# BeagleBeer.net
KiCad netlist of a schematic drawn in EAGLE
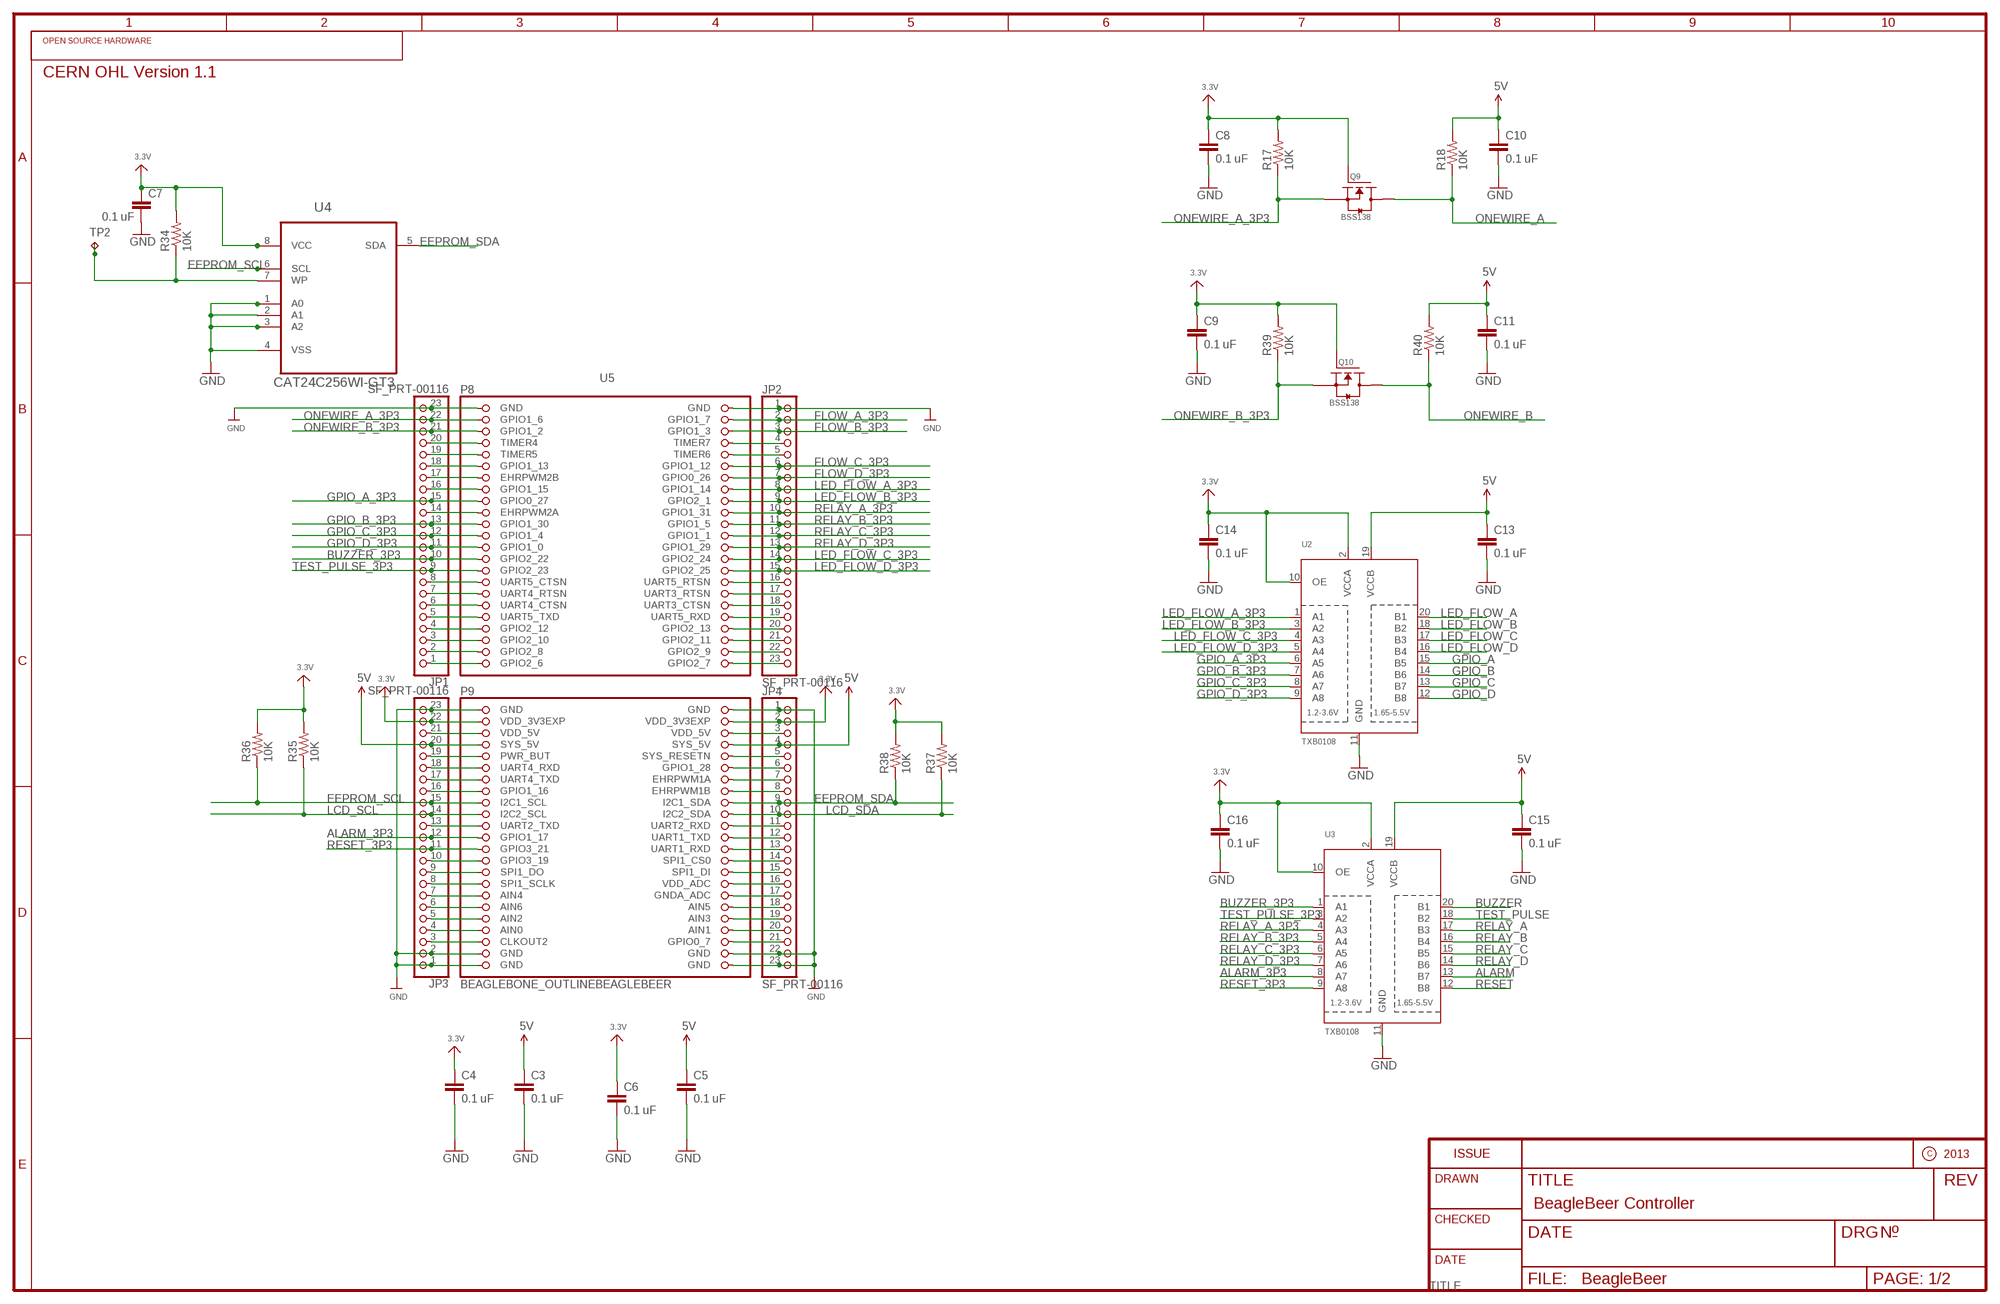
[diagram p0: schematic, sheet 1]
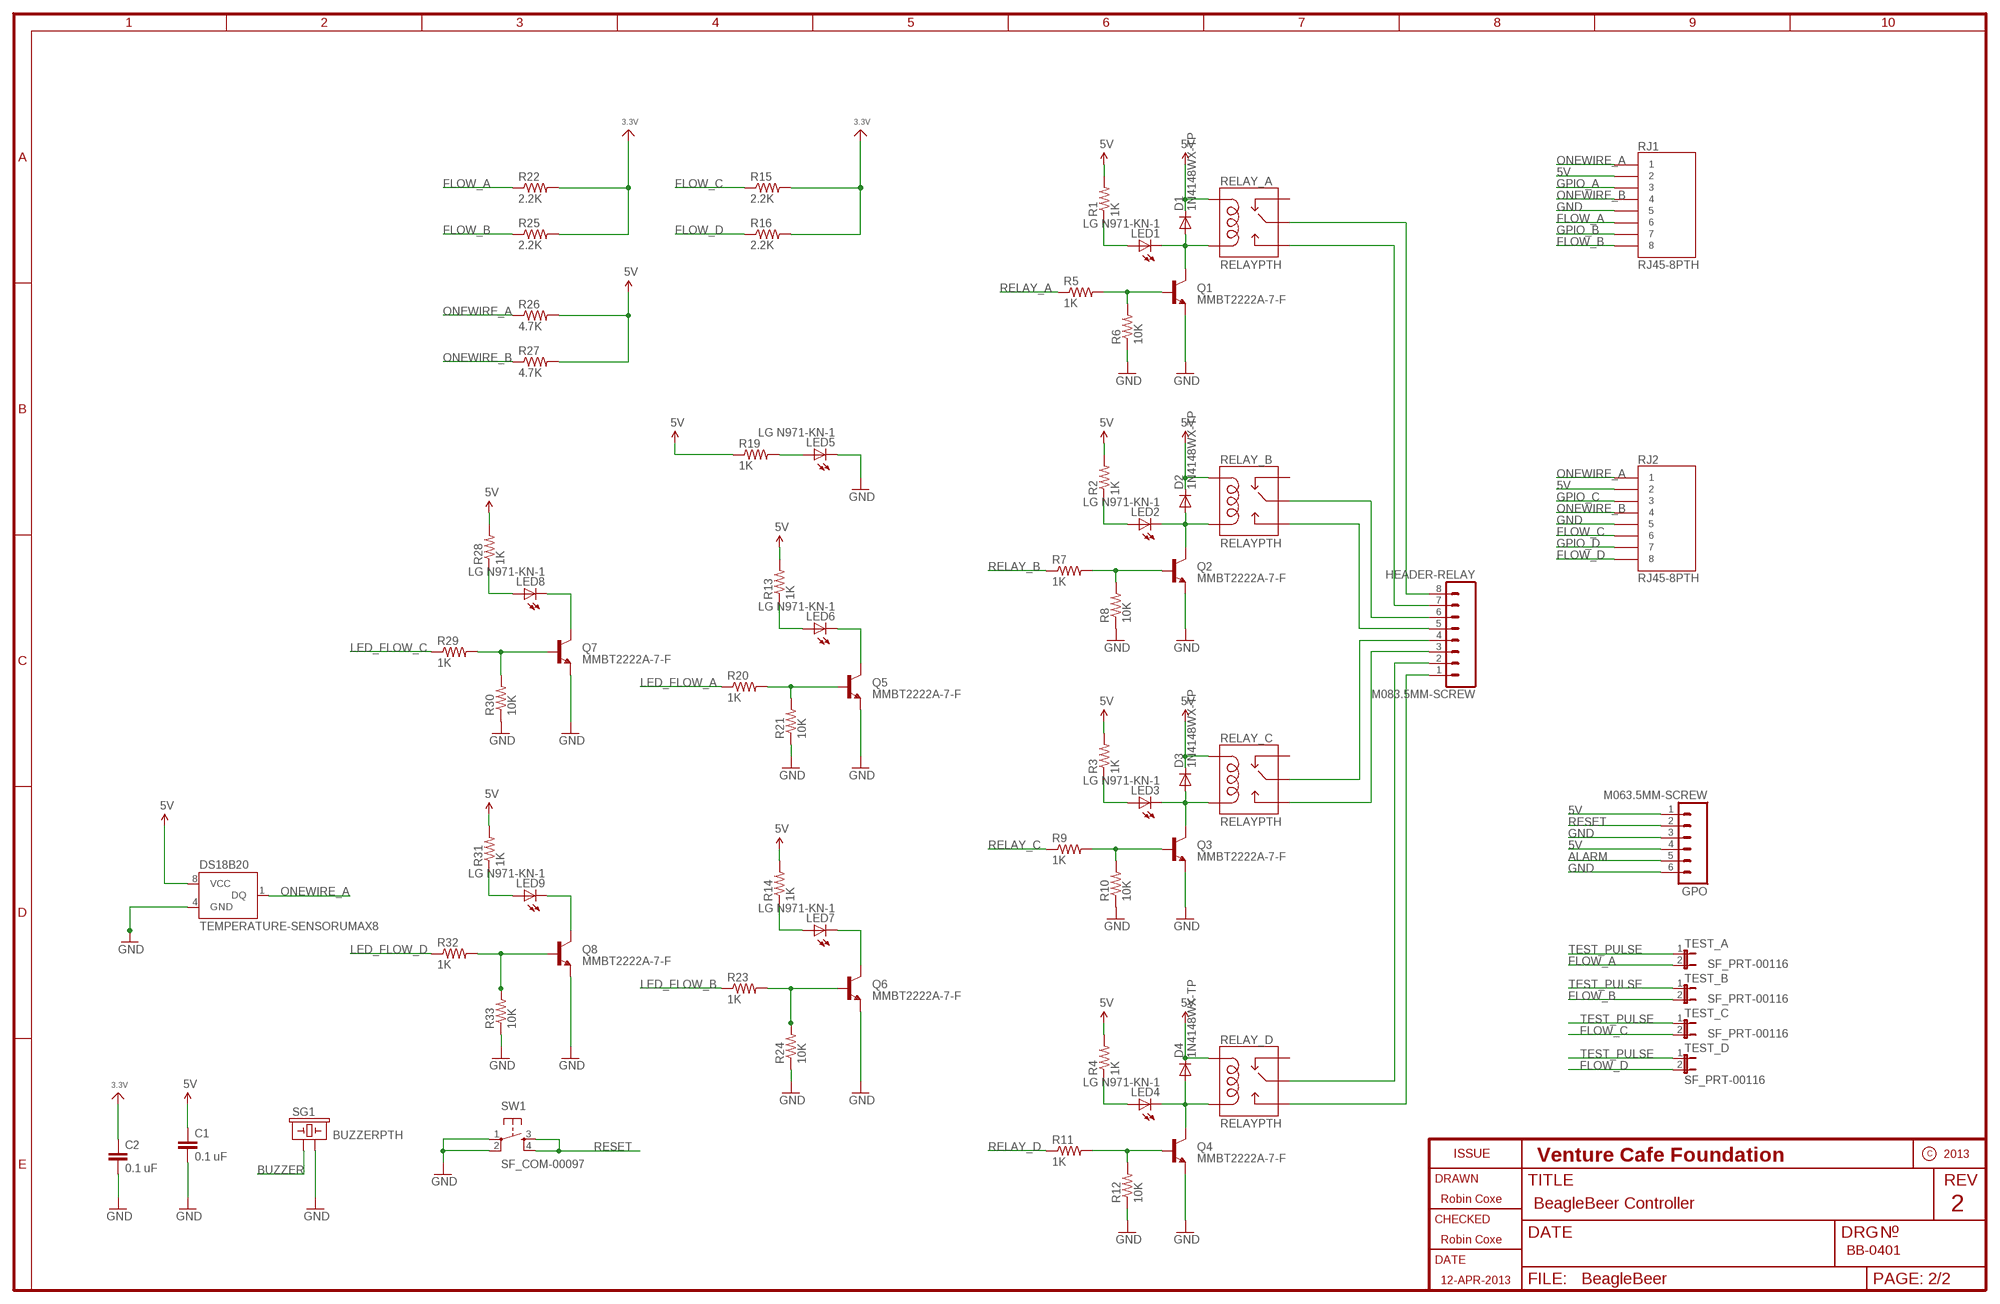
[diagram p1: schematic, sheet 2]

(export (version "E")
  (design (tool "Eeschema 10.0.6"))
  (components
    (comp (ref "C1")
      (value "0.1 uF")
      (footprint "eagle-import:0805")
      (libsource (lib "eagle-import") (part "CAP0805"))
    )
    (comp (ref "C2")
      (value "0.1 uF")
      (footprint "eagle-import:0805")
      (libsource (lib "eagle-import") (part "CAP0805"))
    )
    (comp (ref "D1")
      (value "1N4148WX-TP")
      (footprint "eagle-import:SOD-323")
      (libsource (lib "eagle-import") (part "DIODESOD"))
    )
    (comp (ref "D2")
      (value "1N4148WX-TP")
      (footprint "eagle-import:SOD-323")
      (libsource (lib "eagle-import") (part "DIODESOD"))
    )
    (comp (ref "D3")
      (value "1N4148WX-TP")
      (footprint "eagle-import:SOD-323")
      (libsource (lib "eagle-import") (part "DIODESOD"))
    )
    (comp (ref "D4")
      (value "1N4148WX-TP")
      (footprint "eagle-import:SOD-323")
      (libsource (lib "eagle-import") (part "DIODESOD"))
    )
    (comp (ref "GPO")
      (value "M063.5MM-SCREW")
      (footprint "eagle-import:SCREWTERMINAL-3.5MM-6")
      (libsource (lib "eagle-import") (part "M063.5MM-6"))
    )
    (comp (ref "HEADER-RELAY")
      (value "M083.5MM-SCREW")
      (footprint "eagle-import:SCREWTERMINAL-3.5MM-8")
      (libsource (lib "eagle-import") (part "M083.5MM-8"))
    )
    (comp (ref "LED1")
      (value "LG N971-KN-1")
      (footprint "eagle-import:LED-1206")
      (libsource (lib "eagle-import") (part "LED1206"))
    )
    (comp (ref "LED2")
      (value "LG N971-KN-1")
      (footprint "eagle-import:LED-1206")
      (libsource (lib "eagle-import") (part "LED1206"))
    )
    (comp (ref "LED3")
      (value "LG N971-KN-1")
      (footprint "eagle-import:LED-1206")
      (libsource (lib "eagle-import") (part "LED1206"))
    )
    (comp (ref "LED4")
      (value "LG N971-KN-1")
      (footprint "eagle-import:LED-1206")
      (libsource (lib "eagle-import") (part "LED1206"))
    )
    (comp (ref "LED5")
      (value "LG N971-KN-1")
      (footprint "eagle-import:LED-1206")
      (libsource (lib "eagle-import") (part "LED1206"))
    )
    (comp (ref "LED6")
      (value "LG N971-KN-1")
      (footprint "eagle-import:LED-1206")
      (libsource (lib "eagle-import") (part "LED1206"))
    )
    (comp (ref "LED7")
      (value "LG N971-KN-1")
      (footprint "eagle-import:LED-1206")
      (libsource (lib "eagle-import") (part "LED1206"))
    )
    (comp (ref "LED8")
      (value "LG N971-KN-1")
      (footprint "eagle-import:LED-1206")
      (libsource (lib "eagle-import") (part "LED1206"))
    )
    (comp (ref "LED9")
      (value "LG N971-KN-1")
      (footprint "eagle-import:LED-1206")
      (libsource (lib "eagle-import") (part "LED1206"))
    )
    (comp (ref "Q1")
      (value "MMBT2222A-7-F")
      (footprint "eagle-import:SOT23-3")
      (libsource (lib "eagle-import") (part "TRANSISTOR_NPNSOT23-3"))
    )
    (comp (ref "Q2")
      (value "MMBT2222A-7-F")
      (footprint "eagle-import:SOT23-3")
      (libsource (lib "eagle-import") (part "TRANSISTOR_NPNSOT23-3"))
    )
    (comp (ref "Q3")
      (value "MMBT2222A-7-F")
      (footprint "eagle-import:SOT23-3")
      (libsource (lib "eagle-import") (part "TRANSISTOR_NPNSOT23-3"))
    )
    (comp (ref "Q4")
      (value "MMBT2222A-7-F")
      (footprint "eagle-import:SOT23-3")
      (libsource (lib "eagle-import") (part "TRANSISTOR_NPNSOT23-3"))
    )
    (comp (ref "Q5")
      (value "MMBT2222A-7-F")
      (footprint "eagle-import:SOT23-3")
      (libsource (lib "eagle-import") (part "TRANSISTOR_NPNSOT23-3"))
    )
    (comp (ref "Q6")
      (value "MMBT2222A-7-F")
      (footprint "eagle-import:SOT23-3")
      (libsource (lib "eagle-import") (part "TRANSISTOR_NPNSOT23-3"))
    )
    (comp (ref "Q7")
      (value "MMBT2222A-7-F")
      (footprint "eagle-import:SOT23-3")
      (libsource (lib "eagle-import") (part "TRANSISTOR_NPNSOT23-3"))
    )
    (comp (ref "Q8")
      (value "MMBT2222A-7-F")
      (footprint "eagle-import:SOT23-3")
      (libsource (lib "eagle-import") (part "TRANSISTOR_NPNSOT23-3"))
    )
    (comp (ref "R1")
      (value "1K")
      (footprint "eagle-import:0805")
      (libsource (lib "eagle-import") (part "RESISTOR0805-RES"))
    )
    (comp (ref "R2")
      (value "1K")
      (footprint "eagle-import:0805")
      (libsource (lib "eagle-import") (part "RESISTOR0805-RES"))
    )
    (comp (ref "R3")
      (value "1K")
      (footprint "eagle-import:0805")
      (libsource (lib "eagle-import") (part "RESISTOR0805-RES"))
    )
    (comp (ref "R4")
      (value "1K")
      (footprint "eagle-import:0805")
      (libsource (lib "eagle-import") (part "RESISTOR0805-RES"))
    )
    (comp (ref "R5")
      (value "1K")
      (footprint "eagle-import:0805")
      (libsource (lib "eagle-import") (part "RESISTOR0805-RES"))
    )
    (comp (ref "R6")
      (value "10K")
      (footprint "eagle-import:0805")
      (libsource (lib "eagle-import") (part "RESISTOR0805-RES"))
    )
    (comp (ref "R7")
      (value "1K")
      (footprint "eagle-import:0805")
      (libsource (lib "eagle-import") (part "RESISTOR0805-RES"))
    )
    (comp (ref "R8")
      (value "10K")
      (footprint "eagle-import:0805")
      (libsource (lib "eagle-import") (part "RESISTOR0805-RES"))
    )
    (comp (ref "R9")
      (value "1K")
      (footprint "eagle-import:0805")
      (libsource (lib "eagle-import") (part "RESISTOR0805-RES"))
    )
    (comp (ref "R10")
      (value "10K")
      (footprint "eagle-import:0805")
      (libsource (lib "eagle-import") (part "RESISTOR0805-RES"))
    )
    (comp (ref "R11")
      (value "1K")
      (footprint "eagle-import:0805")
      (libsource (lib "eagle-import") (part "RESISTOR0805-RES"))
    )
    (comp (ref "R12")
      (value "10K")
      (footprint "eagle-import:0805")
      (libsource (lib "eagle-import") (part "RESISTOR0805-RES"))
    )
    (comp (ref "R13")
      (value "1K")
      (footprint "eagle-import:0805")
      (libsource (lib "eagle-import") (part "RESISTOR0805-RES"))
    )
    (comp (ref "R14")
      (value "1K")
      (footprint "eagle-import:0805")
      (libsource (lib "eagle-import") (part "RESISTOR0805-RES"))
    )
    (comp (ref "R15")
      (value "2.2K")
      (footprint "eagle-import:0805")
      (libsource (lib "eagle-import") (part "RESISTOR0805-RES"))
    )
    (comp (ref "R16")
      (value "2.2K")
      (footprint "eagle-import:0805")
      (libsource (lib "eagle-import") (part "RESISTOR0805-RES"))
    )
    (comp (ref "R19")
      (value "1K")
      (footprint "eagle-import:0805")
      (libsource (lib "eagle-import") (part "RESISTOR0805-RES"))
    )
    (comp (ref "R20")
      (value "1K")
      (footprint "eagle-import:0805")
      (libsource (lib "eagle-import") (part "RESISTOR0805-RES"))
    )
    (comp (ref "R21")
      (value "10K")
      (footprint "eagle-import:0805")
      (libsource (lib "eagle-import") (part "RESISTOR0805-RES"))
    )
    (comp (ref "R22")
      (value "2.2K")
      (footprint "eagle-import:0805")
      (libsource (lib "eagle-import") (part "RESISTOR0805-RES"))
    )
    (comp (ref "R23")
      (value "1K")
      (footprint "eagle-import:0805")
      (libsource (lib "eagle-import") (part "RESISTOR0805-RES"))
    )
    (comp (ref "R24")
      (value "10K")
      (footprint "eagle-import:0805")
      (libsource (lib "eagle-import") (part "RESISTOR0805-RES"))
    )
    (comp (ref "R25")
      (value "2.2K")
      (footprint "eagle-import:0805")
      (libsource (lib "eagle-import") (part "RESISTOR0805-RES"))
    )
    (comp (ref "R26")
      (value "4.7K")
      (footprint "eagle-import:0805")
      (libsource (lib "eagle-import") (part "RESISTOR0805-RES"))
    )
    (comp (ref "R27")
      (value "4.7K")
      (footprint "eagle-import:0805")
      (libsource (lib "eagle-import") (part "RESISTOR0805-RES"))
    )
    (comp (ref "R28")
      (value "1K")
      (footprint "eagle-import:0805")
      (libsource (lib "eagle-import") (part "RESISTOR0805-RES"))
    )
    (comp (ref "R29")
      (value "1K")
      (footprint "eagle-import:0805")
      (libsource (lib "eagle-import") (part "RESISTOR0805-RES"))
    )
    (comp (ref "R30")
      (value "10K")
      (footprint "eagle-import:0805")
      (libsource (lib "eagle-import") (part "RESISTOR0805-RES"))
    )
    (comp (ref "R31")
      (value "1K")
      (footprint "eagle-import:0805")
      (libsource (lib "eagle-import") (part "RESISTOR0805-RES"))
    )
    (comp (ref "R32")
      (value "1K")
      (footprint "eagle-import:0805")
      (libsource (lib "eagle-import") (part "RESISTOR0805-RES"))
    )
    (comp (ref "R33")
      (value "10K")
      (footprint "eagle-import:0805")
      (libsource (lib "eagle-import") (part "RESISTOR0805-RES"))
    )
    (comp (ref "RELAY_A")
      (value "RELAYPTH")
      (footprint "eagle-import:RELAY-G5Q")
      (libsource (lib "eagle-import") (part "RELAYPTH"))
    )
    (comp (ref "RELAY_B")
      (value "RELAYPTH")
      (footprint "eagle-import:RELAY-G5Q")
      (libsource (lib "eagle-import") (part "RELAYPTH"))
    )
    (comp (ref "RELAY_C")
      (value "RELAYPTH")
      (footprint "eagle-import:RELAY-G5Q")
      (libsource (lib "eagle-import") (part "RELAYPTH"))
    )
    (comp (ref "RELAY_D")
      (value "RELAYPTH")
      (footprint "eagle-import:RELAY-G5Q")
      (libsource (lib "eagle-import") (part "RELAYPTH"))
    )
    (comp (ref "RJ1")
      (value "RJ45-8PTH")
      (footprint "eagle-import:RJ45-8")
      (libsource (lib "eagle-import") (part "RJ45-8PTH"))
    )
    (comp (ref "RJ2")
      (value "RJ45-8PTH")
      (footprint "eagle-import:RJ45-8")
      (libsource (lib "eagle-import") (part "RJ45-8PTH"))
    )
    (comp (ref "SG1")
      (value "BUZZERPTH")
      (footprint "eagle-import:BUZZER-12MM")
      (libsource (lib "eagle-import") (part "BUZZERPTH"))
    )
    (comp (ref "SW1")
      (value "SF_COM-00097")
      (footprint "eagle-import:TACTILE-PTH")
      (libsource (lib "eagle-import") (part "TAC_SWITCHPTH"))
    )
    (comp (ref "TEST_A")
      (value "SF_PRT-00116")
      (footprint "eagle-import:1X02")
      (libsource (lib "eagle-import") (part "JUMPER-2PTH"))
    )
    (comp (ref "TEST_B")
      (value "SF_PRT-00116")
      (footprint "eagle-import:1X02")
      (libsource (lib "eagle-import") (part "JUMPER-2PTH"))
    )
    (comp (ref "TEST_C")
      (value "SF_PRT-00116")
      (footprint "eagle-import:1X02")
      (libsource (lib "eagle-import") (part "JUMPER-2PTH"))
    )
    (comp (ref "TEST_D")
      (value "SF_PRT-00116")
      (footprint "eagle-import:1X02")
      (libsource (lib "eagle-import") (part "JUMPER-2PTH"))
    )
    (comp (ref "U1")
      (value "TEMPERATURE-SENSORUMAX8")
      (footprint "eagle-import:UMAX8")
      (libsource (lib "eagle-import") (part "TEMPERATURE-SENSORUMAX8"))
    )
    (comp (ref "C3")
      (value "0.1 uF")
      (footprint "eagle-import:0805")
      (libsource (lib "eagle-import") (part "CAP0805"))
    )
    (comp (ref "C4")
      (value "0.1 uF")
      (footprint "eagle-import:0805")
      (libsource (lib "eagle-import") (part "CAP0805"))
    )
    (comp (ref "C5")
      (value "0.1 uF")
      (footprint "eagle-import:0805")
      (libsource (lib "eagle-import") (part "CAP0805"))
    )
    (comp (ref "C6")
      (value "0.1 uF")
      (footprint "eagle-import:0805")
      (libsource (lib "eagle-import") (part "CAP0805"))
    )
    (comp (ref "C7")
      (value "0.1 uF")
      (footprint "eagle-import:0805")
      (libsource (lib "eagle-import") (part "CAP0805"))
    )
    (comp (ref "C8")
      (value "0.1 uF")
      (footprint "eagle-import:0805")
      (libsource (lib "eagle-import") (part "CAP0805"))
    )
    (comp (ref "C9")
      (value "0.1 uF")
      (footprint "eagle-import:0805")
      (libsource (lib "eagle-import") (part "CAP0805"))
    )
    (comp (ref "C10")
      (value "0.1 uF")
      (footprint "eagle-import:0805")
      (libsource (lib "eagle-import") (part "CAP0805"))
    )
    (comp (ref "C11")
      (value "0.1 uF")
      (footprint "eagle-import:0805")
      (libsource (lib "eagle-import") (part "CAP0805"))
    )
    (comp (ref "C13")
      (value "0.1 uF")
      (footprint "eagle-import:0805")
      (libsource (lib "eagle-import") (part "CAP0805"))
    )
    (comp (ref "C14")
      (value "0.1 uF")
      (footprint "eagle-import:0805")
      (libsource (lib "eagle-import") (part "CAP0805"))
    )
    (comp (ref "C15")
      (value "0.1 uF")
      (footprint "eagle-import:0805")
      (libsource (lib "eagle-import") (part "CAP0805"))
    )
    (comp (ref "C16")
      (value "0.1 uF")
      (footprint "eagle-import:0805")
      (libsource (lib "eagle-import") (part "CAP0805"))
    )
    (comp (ref "JP1")
      (value "SF_PRT-00116")
      (footprint "eagle-import:1X23_ROUND_70MIL")
      (libsource (lib "eagle-import") (part "HEADER-1X23"))
    )
    (comp (ref "JP2")
      (value "SF_PRT-00116")
      (footprint "eagle-import:1X23_ROUND_70MIL")
      (libsource (lib "eagle-import") (part "HEADER-1X23"))
    )
    (comp (ref "JP3")
      (value "SF_PRT-00116")
      (footprint "eagle-import:1X23_ROUND_70MIL")
      (libsource (lib "eagle-import") (part "HEADER-1X23"))
    )
    (comp (ref "JP4")
      (value "SF_PRT-00116")
      (footprint "eagle-import:1X23_ROUND_70MIL")
      (libsource (lib "eagle-import") (part "HEADER-1X23"))
    )
    (comp (ref "Q9")
      (value "BSS138")
      (footprint "eagle-import:SOT323")
      (libsource (lib "eagle-import") (part "MOSFET-N-GDS-D-SOT323"))
    )
    (comp (ref "Q10")
      (value "BSS138")
      (footprint "eagle-import:SOT323")
      (libsource (lib "eagle-import") (part "MOSFET-N-GDS-D-SOT323"))
    )
    (comp (ref "R17")
      (value "10K")
      (footprint "eagle-import:0805")
      (libsource (lib "eagle-import") (part "RESISTOR0805-RES"))
    )
    (comp (ref "R18")
      (value "10K")
      (footprint "eagle-import:0805")
      (libsource (lib "eagle-import") (part "RESISTOR0805-RES"))
    )
    (comp (ref "R34")
      (value "10K")
      (footprint "eagle-import:0805")
      (libsource (lib "eagle-import") (part "RESISTOR0805-RES"))
    )
    (comp (ref "R35")
      (value "10K")
      (footprint "eagle-import:0805")
      (libsource (lib "eagle-import") (part "RESISTOR0805-RES"))
    )
    (comp (ref "R36")
      (value "10K")
      (footprint "eagle-import:0805")
      (libsource (lib "eagle-import") (part "RESISTOR0805-RES"))
    )
    (comp (ref "R37")
      (value "10K")
      (footprint "eagle-import:0805")
      (libsource (lib "eagle-import") (part "RESISTOR0805-RES"))
    )
    (comp (ref "R38")
      (value "10K")
      (footprint "eagle-import:0805")
      (libsource (lib "eagle-import") (part "RESISTOR0805-RES"))
    )
    (comp (ref "R39")
      (value "10K")
      (footprint "eagle-import:0805")
      (libsource (lib "eagle-import") (part "RESISTOR0805-RES"))
    )
    (comp (ref "R40")
      (value "10K")
      (footprint "eagle-import:0805")
      (libsource (lib "eagle-import") (part "RESISTOR0805-RES"))
    )
    (comp (ref "TP2")
      (value "TPTP18SQ")
      (footprint "eagle-import:TP18SQ")
      (libsource (lib "eagle-import") (part "TPTP18SQ"))
    )
    (comp (ref "U2")
      (value "TXB0108")
      (footprint "eagle-import:TSSOP20")
      (libsource (lib "eagle-import") (part "TXB0108PWR"))
    )
    (comp (ref "U3")
      (value "TXB0108")
      (footprint "eagle-import:TSSOP20")
      (libsource (lib "eagle-import") (part "TXB0108PWR"))
    )
    (comp (ref "U4")
      (value "CAT24C256WI-GT3")
      (footprint "eagle-import:SOIC127P600X175-8N")
      (libsource (lib "eagle-import") (part "CAT24C256WI-GT3"))
    )
    (comp (ref "U5")
      (value "BEAGLEBONE_OUTLINEBEAGLEBEER")
      (footprint "eagle-import:BEAGLEBEER_SHIELD")
      (libsource (lib "eagle-import") (part "BEAGLEBONE_OUTLINEBEAGLEBEER"))
    )
  )
  (nets
    (net (code "1") (name "3.3V") (class "Default")
      (node (ref "C14") (pin "1") (pinfunction "1_1") (pintype "passive"))
      (node (ref "C16") (pin "1") (pinfunction "1_1") (pintype "passive"))
      (node (ref "C2") (pin "1") (pinfunction "1_1") (pintype "passive"))
      (node (ref "C4") (pin "1") (pinfunction "1_1") (pintype "passive"))
      (node (ref "C6") (pin "1") (pinfunction "1_1") (pintype "passive"))
      (node (ref "C7") (pin "1") (pinfunction "1_1") (pintype "passive"))
      (node (ref "C8") (pin "1") (pinfunction "1_1") (pintype "passive"))
      (node (ref "C9") (pin "1") (pinfunction "1_1") (pintype "passive"))
      (node (ref "JP3") (pin "22") (pinfunction "22_22") (pintype "passive"))
      (node (ref "JP4") (pin "2") (pinfunction "2_2") (pintype "passive"))
      (node (ref "Q10") (pin "1") (pinfunction "G_1") (pintype "passive"))
      (node (ref "Q9") (pin "1") (pinfunction "G_1") (pintype "passive"))
      (node (ref "R15") (pin "2") (pinfunction "2_2") (pintype "passive"))
      (node (ref "R16") (pin "2") (pinfunction "2_2") (pintype "passive"))
      (node (ref "R17") (pin "2") (pinfunction "2_2") (pintype "passive"))
      (node (ref "R22") (pin "2") (pinfunction "2_2") (pintype "passive"))
      (node (ref "R25") (pin "2") (pinfunction "2_2") (pintype "passive"))
      (node (ref "R34") (pin "2") (pinfunction "2_2") (pintype "passive"))
      (node (ref "R35") (pin "2") (pinfunction "2_2") (pintype "passive"))
      (node (ref "R36") (pin "2") (pinfunction "2_2") (pintype "passive"))
      (node (ref "R37") (pin "2") (pinfunction "2_2") (pintype "passive"))
      (node (ref "R38") (pin "2") (pinfunction "2_2") (pintype "passive"))
      (node (ref "R39") (pin "2") (pinfunction "2_2") (pintype "passive"))
      (node (ref "U2") (pin "10") (pinfunction "OE_10") (pintype "bidirectional"))
      (node (ref "U2") (pin "2") (pinfunction "VCCA_2") (pintype "bidirectional"))
      (node (ref "U3") (pin "10") (pinfunction "OE_10") (pintype "bidirectional"))
      (node (ref "U3") (pin "2") (pinfunction "VCCA_2") (pintype "bidirectional"))
      (node (ref "U4") (pin "8") (pinfunction "VCC_8") (pintype "power_in"))
      (node (ref "U5") (pin "49") (pinfunction "VDD_3V3EXP_49") (pintype "power_in"))
      (node (ref "U5") (pin "50") (pinfunction "VDD_3V3EXP_50") (pintype "power_in"))
    )
    (net (code "2") (name "5V") (class "Default")
      (node (ref "C1") (pin "1") (pinfunction "1_1") (pintype "passive"))
      (node (ref "C10") (pin "1") (pinfunction "1_1") (pintype "passive"))
      (node (ref "C11") (pin "1") (pinfunction "1_1") (pintype "passive"))
      (node (ref "C13") (pin "1") (pinfunction "1_1") (pintype "passive"))
      (node (ref "C15") (pin "1") (pinfunction "1_1") (pintype "passive"))
      (node (ref "C3") (pin "1") (pinfunction "1_1") (pintype "passive"))
      (node (ref "C5") (pin "1") (pinfunction "1_1") (pintype "passive"))
      (node (ref "D1") (pin "1") (pinfunction "C_1") (pintype "passive"))
      (node (ref "D2") (pin "1") (pinfunction "C_1") (pintype "passive"))
      (node (ref "D3") (pin "1") (pinfunction "C_1") (pintype "passive"))
      (node (ref "D4") (pin "1") (pinfunction "C_1") (pintype "passive"))
      (node (ref "GPO") (pin "1") (pinfunction "1_1") (pintype "passive"))
      (node (ref "GPO") (pin "4") (pinfunction "4_4") (pintype "passive"))
      (node (ref "JP3") (pin "20") (pinfunction "20_20") (pintype "passive"))
      (node (ref "JP4") (pin "4") (pinfunction "4_4") (pintype "passive"))
      (node (ref "R1") (pin "2") (pinfunction "2_2") (pintype "passive"))
      (node (ref "R13") (pin "2") (pinfunction "2_2") (pintype "passive"))
      (node (ref "R14") (pin "2") (pinfunction "2_2") (pintype "passive"))
      (node (ref "R18") (pin "2") (pinfunction "2_2") (pintype "passive"))
      (node (ref "R19") (pin "1") (pinfunction "1_1") (pintype "passive"))
      (node (ref "R2") (pin "2") (pinfunction "2_2") (pintype "passive"))
      (node (ref "R26") (pin "2") (pinfunction "2_2") (pintype "passive"))
      (node (ref "R27") (pin "2") (pinfunction "2_2") (pintype "passive"))
      (node (ref "R28") (pin "2") (pinfunction "2_2") (pintype "passive"))
      (node (ref "R3") (pin "2") (pinfunction "2_2") (pintype "passive"))
      (node (ref "R31") (pin "2") (pinfunction "2_2") (pintype "passive"))
      (node (ref "R4") (pin "2") (pinfunction "2_2") (pintype "passive"))
      (node (ref "R40") (pin "2") (pinfunction "2_2") (pintype "passive"))
      (node (ref "RELAY_A") (pin "5") (pinfunction "COIL1_5") (pintype "bidirectional"))
      (node (ref "RELAY_B") (pin "5") (pinfunction "COIL1_5") (pintype "bidirectional"))
      (node (ref "RELAY_C") (pin "5") (pinfunction "COIL1_5") (pintype "bidirectional"))
      (node (ref "RELAY_D") (pin "5") (pinfunction "COIL1_5") (pintype "bidirectional"))
      (node (ref "RJ1") (pin "2") (pinfunction "2_2") (pintype "bidirectional"))
      (node (ref "RJ2") (pin "2") (pinfunction "2_2") (pintype "bidirectional"))
      (node (ref "U1") (pin "8") (pinfunction "VCC_8") (pintype "bidirectional"))
      (node (ref "U2") (pin "19") (pinfunction "VCCB_19") (pintype "bidirectional"))
      (node (ref "U3") (pin "19") (pinfunction "VCCB_19") (pintype "bidirectional"))
      (node (ref "U5") (pin "53") (pinfunction "SYS_5V_53") (pintype "passive"))
      (node (ref "U5") (pin "54") (pinfunction "SYS_5V_54") (pintype "passive"))
    )
    (net (code "3") (name "ALARM") (class "Default")
      (node (ref "GPO") (pin "5") (pinfunction "5_5") (pintype "passive"))
      (node (ref "U3") (pin "13") (pinfunction "B7_13") (pintype "bidirectional"))
    )
    (net (code "4") (name "ALARM_3P3") (class "Default")
      (node (ref "JP3") (pin "12") (pinfunction "12_12") (pintype "passive"))
      (node (ref "U3") (pin "8") (pinfunction "A7_8") (pintype "bidirectional"))
      (node (ref "U5") (pin "69") (pinfunction "GPIO1_17_69") (pintype "passive"))
    )
    (net (code "5") (name "BUZZER") (class "Default")
      (node (ref "SG1") (pin "+") (pinfunction "1_+") (pintype "passive"))
      (node (ref "U3") (pin "20") (pinfunction "B1_20") (pintype "bidirectional"))
    )
    (net (code "6") (name "BUZZER_3P3") (class "Default")
      (node (ref "JP1") (pin "10") (pinfunction "10_10") (pintype "passive"))
      (node (ref "U3") (pin "1") (pinfunction "A1_1") (pintype "bidirectional"))
      (node (ref "U5") (pin "27") (pinfunction "GPIO2_22_27") (pintype "passive"))
    )
    (net (code "7") (name "EEPROM_SCL") (class "Default")
      (node (ref "JP3") (pin "15") (pinfunction "15_15") (pintype "passive"))
      (node (ref "R36") (pin "1") (pinfunction "1_1") (pintype "passive"))
      (node (ref "U4") (pin "6") (pinfunction "SCL_6") (pintype "input"))
      (node (ref "U5") (pin "63") (pinfunction "I2C1_SCL_63") (pintype "passive"))
    )
    (net (code "8") (name "EEPROM_SDA") (class "Default")
      (node (ref "JP4") (pin "9") (pinfunction "9_9") (pintype "passive"))
      (node (ref "R38") (pin "1") (pinfunction "1_1") (pintype "passive"))
      (node (ref "U4") (pin "5") (pinfunction "SDA_5") (pintype "bidirectional"))
      (node (ref "U5") (pin "64") (pinfunction "I2C1_SDA_64") (pintype "passive"))
    )
    (net (code "9") (name "FLOW_A") (class "Default")
      (node (ref "R22") (pin "1") (pinfunction "1_1") (pintype "passive"))
      (node (ref "RJ1") (pin "6") (pinfunction "6_6") (pintype "bidirectional"))
      (node (ref "TEST_A") (pin "2") (pinfunction "2_2") (pintype "passive"))
    )
    (net (code "10") (name "FLOW_A_3P3") (class "Default")
      (node (ref "JP2") (pin "2") (pinfunction "2_2") (pintype "passive"))
      (node (ref "U5") (pin "4") (pinfunction "GPIO1_7_4") (pintype "power_in"))
    )
    (net (code "11") (name "FLOW_B") (class "Default")
      (node (ref "R25") (pin "1") (pinfunction "1_1") (pintype "passive"))
      (node (ref "RJ1") (pin "8") (pinfunction "8_8") (pintype "bidirectional"))
      (node (ref "TEST_B") (pin "2") (pinfunction "2_2") (pintype "passive"))
    )
    (net (code "12") (name "FLOW_B_3P3") (class "Default")
      (node (ref "JP2") (pin "3") (pinfunction "3_3") (pintype "passive"))
      (node (ref "U5") (pin "6") (pinfunction "GPIO1_3_6") (pintype "passive"))
    )
    (net (code "13") (name "FLOW_C") (class "Default")
      (node (ref "R15") (pin "1") (pinfunction "1_1") (pintype "passive"))
      (node (ref "RJ2") (pin "6") (pinfunction "6_6") (pintype "bidirectional"))
      (node (ref "TEST_C") (pin "2") (pinfunction "2_2") (pintype "passive"))
    )
    (net (code "14") (name "FLOW_C_3P3") (class "Default")
      (node (ref "JP2") (pin "6") (pinfunction "6_6") (pintype "passive"))
      (node (ref "U5") (pin "12") (pinfunction "GPIO1_12_12") (pintype "passive"))
    )
    (net (code "15") (name "FLOW_D") (class "Default")
      (node (ref "R16") (pin "1") (pinfunction "1_1") (pintype "passive"))
      (node (ref "RJ2") (pin "8") (pinfunction "8_8") (pintype "bidirectional"))
      (node (ref "TEST_D") (pin "2") (pinfunction "2_2") (pintype "passive"))
    )
    (net (code "16") (name "FLOW_D_3P3") (class "Default")
      (node (ref "JP2") (pin "7") (pinfunction "7_7") (pintype "passive"))
      (node (ref "U5") (pin "14") (pinfunction "GPIO0_26_14") (pintype "passive"))
    )
    (net (code "17") (name "GND") (class "Default")
      (node (ref "C1") (pin "2") (pinfunction "2_2") (pintype "passive"))
      (node (ref "C10") (pin "2") (pinfunction "2_2") (pintype "passive"))
      (node (ref "C11") (pin "2") (pinfunction "2_2") (pintype "passive"))
      (node (ref "C13") (pin "2") (pinfunction "2_2") (pintype "passive"))
      (node (ref "C14") (pin "2") (pinfunction "2_2") (pintype "passive"))
      (node (ref "C15") (pin "2") (pinfunction "2_2") (pintype "passive"))
      (node (ref "C16") (pin "2") (pinfunction "2_2") (pintype "passive"))
      (node (ref "C2") (pin "2") (pinfunction "2_2") (pintype "passive"))
      (node (ref "C3") (pin "2") (pinfunction "2_2") (pintype "passive"))
      (node (ref "C4") (pin "2") (pinfunction "2_2") (pintype "passive"))
      (node (ref "C5") (pin "2") (pinfunction "2_2") (pintype "passive"))
      (node (ref "C6") (pin "2") (pinfunction "2_2") (pintype "passive"))
      (node (ref "C7") (pin "2") (pinfunction "2_2") (pintype "passive"))
      (node (ref "C8") (pin "2") (pinfunction "2_2") (pintype "passive"))
      (node (ref "C9") (pin "2") (pinfunction "2_2") (pintype "passive"))
      (node (ref "GPO") (pin "3") (pinfunction "3_3") (pintype "passive"))
      (node (ref "GPO") (pin "6") (pinfunction "6_6") (pintype "passive"))
      (node (ref "JP1") (pin "23") (pinfunction "23_23") (pintype "passive"))
      (node (ref "JP2") (pin "1") (pinfunction "1_1") (pintype "passive"))
      (node (ref "JP3") (pin "1") (pinfunction "1_1") (pintype "passive"))
      (node (ref "JP3") (pin "2") (pinfunction "2_2") (pintype "passive"))
      (node (ref "JP3") (pin "23") (pinfunction "23_23") (pintype "passive"))
      (node (ref "JP4") (pin "1") (pinfunction "1_1") (pintype "passive"))
      (node (ref "JP4") (pin "22") (pinfunction "22_22") (pintype "passive"))
      (node (ref "JP4") (pin "23") (pinfunction "23_23") (pintype "passive"))
      (node (ref "LED5") (pin "C") (pinfunction "C_C") (pintype "passive"))
      (node (ref "Q1") (pin "2") (pinfunction "E_2") (pintype "passive"))
      (node (ref "Q2") (pin "2") (pinfunction "E_2") (pintype "passive"))
      (node (ref "Q3") (pin "2") (pinfunction "E_2") (pintype "passive"))
      (node (ref "Q4") (pin "2") (pinfunction "E_2") (pintype "passive"))
      (node (ref "Q5") (pin "2") (pinfunction "E_2") (pintype "passive"))
      (node (ref "Q6") (pin "2") (pinfunction "E_2") (pintype "passive"))
      (node (ref "Q7") (pin "2") (pinfunction "E_2") (pintype "passive"))
      (node (ref "Q8") (pin "2") (pinfunction "E_2") (pintype "passive"))
      (node (ref "R10") (pin "1") (pinfunction "1_1") (pintype "passive"))
      (node (ref "R12") (pin "1") (pinfunction "1_1") (pintype "passive"))
      (node (ref "R21") (pin "1") (pinfunction "1_1") (pintype "passive"))
      (node (ref "R24") (pin "1") (pinfunction "1_1") (pintype "passive"))
      (node (ref "R30") (pin "1") (pinfunction "1_1") (pintype "passive"))
      (node (ref "R33") (pin "1") (pinfunction "1_1") (pintype "passive"))
      (node (ref "R6") (pin "1") (pinfunction "1_1") (pintype "passive"))
      (node (ref "R8") (pin "1") (pinfunction "1_1") (pintype "passive"))
      (node (ref "RJ1") (pin "5") (pinfunction "5_5") (pintype "bidirectional"))
      (node (ref "RJ2") (pin "5") (pinfunction "5_5") (pintype "bidirectional"))
      (node (ref "SG1") (pin "-") (pinfunction "2_-") (pintype "passive"))
      (node (ref "SW1") (pin "1") (pinfunction "1_1") (pintype "passive"))
      (node (ref "SW1") (pin "2") (pinfunction "2_2") (pintype "passive"))
      (node (ref "U1") (pin "4") (pinfunction "GND_4") (pintype "bidirectional"))
      (node (ref "U2") (pin "11") (pinfunction "GND_11") (pintype "bidirectional"))
      (node (ref "U3") (pin "11") (pinfunction "GND_11") (pintype "bidirectional"))
      (node (ref "U4") (pin "1") (pinfunction "A0_1") (pintype "input"))
      (node (ref "U4") (pin "2") (pinfunction "A1_2") (pintype "input"))
      (node (ref "U4") (pin "3") (pinfunction "A2_3") (pintype "input"))
      (node (ref "U4") (pin "4") (pinfunction "VSS_4") (pintype "passive"))
      (node (ref "U5") (pin "1") (pinfunction "GND_1") (pintype "power_in"))
      (node (ref "U5") (pin "2") (pinfunction "GND_2") (pintype "power_in"))
      (node (ref "U5") (pin "47") (pinfunction "GND_47") (pintype "power_in"))
      (node (ref "U5") (pin "48") (pinfunction "GND_48") (pintype "power_in"))
      (node (ref "U5") (pin "89") (pinfunction "GND_89") (pintype "input"))
      (node (ref "U5") (pin "90") (pinfunction "GND_90") (pintype "input"))
      (node (ref "U5") (pin "91") (pinfunction "GND_91") (pintype "input"))
      (node (ref "U5") (pin "92") (pinfunction "GND_92") (pintype "input"))
    )
    (net (code "18") (name "GPIO_A") (class "Default")
      (node (ref "RJ1") (pin "3") (pinfunction "3_3") (pintype "bidirectional"))
      (node (ref "U2") (pin "15") (pinfunction "B5_15") (pintype "bidirectional"))
    )
    (net (code "19") (name "GPIO_A_3P3") (class "Default")
      (node (ref "JP1") (pin "15") (pinfunction "15_15") (pintype "passive"))
      (node (ref "U2") (pin "6") (pinfunction "A5_6") (pintype "bidirectional"))
      (node (ref "U5") (pin "17") (pinfunction "GPIO0_27_17") (pintype "passive"))
    )
    (net (code "20") (name "GPIO_B") (class "Default")
      (node (ref "RJ1") (pin "7") (pinfunction "7_7") (pintype "bidirectional"))
      (node (ref "U2") (pin "14") (pinfunction "B6_14") (pintype "bidirectional"))
    )
    (net (code "21") (name "GPIO_B_3P3") (class "Default")
      (node (ref "JP1") (pin "13") (pinfunction "13_13") (pintype "passive"))
      (node (ref "U2") (pin "7") (pinfunction "A6_7") (pintype "bidirectional"))
      (node (ref "U5") (pin "21") (pinfunction "GPIO1_30_21") (pintype "passive"))
    )
    (net (code "22") (name "GPIO_C") (class "Default")
      (node (ref "RJ2") (pin "3") (pinfunction "3_3") (pintype "bidirectional"))
      (node (ref "U2") (pin "13") (pinfunction "B7_13") (pintype "bidirectional"))
    )
    (net (code "23") (name "GPIO_C_3P3") (class "Default")
      (node (ref "JP1") (pin "12") (pinfunction "12_12") (pintype "passive"))
      (node (ref "U2") (pin "8") (pinfunction "A7_8") (pintype "bidirectional"))
      (node (ref "U5") (pin "23") (pinfunction "GPIO1_4_23") (pintype "passive"))
    )
    (net (code "24") (name "GPIO_D") (class "Default")
      (node (ref "RJ2") (pin "7") (pinfunction "7_7") (pintype "bidirectional"))
      (node (ref "U2") (pin "12") (pinfunction "B8_12") (pintype "bidirectional"))
    )
    (net (code "25") (name "GPIO_D_3P3") (class "Default")
      (node (ref "JP1") (pin "11") (pinfunction "11_11") (pintype "passive"))
      (node (ref "U2") (pin "9") (pinfunction "A8_9") (pintype "bidirectional"))
      (node (ref "U5") (pin "25") (pinfunction "GPIO1_0_25") (pintype "passive"))
    )
    (net (code "26") (name "LCD_SCL") (class "Default")
      (node (ref "JP3") (pin "14") (pinfunction "14_14") (pintype "passive"))
      (node (ref "R35") (pin "1") (pinfunction "1_1") (pintype "passive"))
      (node (ref "U5") (pin "65") (pinfunction "I2C2_SCL_65") (pintype "passive"))
    )
    (net (code "27") (name "LCD_SDA") (class "Default")
      (node (ref "JP4") (pin "10") (pinfunction "10_10") (pintype "passive"))
      (node (ref "R37") (pin "1") (pinfunction "1_1") (pintype "passive"))
      (node (ref "U5") (pin "66") (pinfunction "I2C2_SDA_66") (pintype "passive"))
    )
    (net (code "28") (name "LED_FLOW_A") (class "Default")
      (node (ref "R20") (pin "1") (pinfunction "1_1") (pintype "passive"))
      (node (ref "U2") (pin "20") (pinfunction "B1_20") (pintype "bidirectional"))
    )
    (net (code "29") (name "LED_FLOW_A_3P3") (class "Default")
      (node (ref "JP2") (pin "8") (pinfunction "8_8") (pintype "passive"))
      (node (ref "U2") (pin "1") (pinfunction "A1_1") (pintype "bidirectional"))
      (node (ref "U5") (pin "16") (pinfunction "GPIO1_14_16") (pintype "passive"))
    )
    (net (code "30") (name "LED_FLOW_B") (class "Default")
      (node (ref "R23") (pin "1") (pinfunction "1_1") (pintype "passive"))
      (node (ref "U2") (pin "18") (pinfunction "B2_18") (pintype "bidirectional"))
    )
    (net (code "31") (name "LED_FLOW_B_3P3") (class "Default")
      (node (ref "JP2") (pin "9") (pinfunction "9_9") (pintype "passive"))
      (node (ref "U2") (pin "3") (pinfunction "A2_3") (pintype "bidirectional"))
      (node (ref "U5") (pin "18") (pinfunction "GPIO2_1_18") (pintype "passive"))
    )
    (net (code "32") (name "LED_FLOW_C") (class "Default")
      (node (ref "R29") (pin "1") (pinfunction "1_1") (pintype "passive"))
      (node (ref "U2") (pin "17") (pinfunction "B3_17") (pintype "bidirectional"))
    )
    (net (code "33") (name "LED_FLOW_C_3P3") (class "Default")
      (node (ref "JP2") (pin "14") (pinfunction "14_14") (pintype "passive"))
      (node (ref "U2") (pin "4") (pinfunction "A3_4") (pintype "bidirectional"))
      (node (ref "U5") (pin "28") (pinfunction "GPIO2_24_28") (pintype "passive"))
    )
    (net (code "34") (name "LED_FLOW_D") (class "Default")
      (node (ref "R32") (pin "1") (pinfunction "1_1") (pintype "passive"))
      (node (ref "U2") (pin "16") (pinfunction "B4_16") (pintype "bidirectional"))
    )
    (net (code "35") (name "LED_FLOW_D_3P3") (class "Default")
      (node (ref "JP2") (pin "15") (pinfunction "15_15") (pintype "passive"))
      (node (ref "U2") (pin "5") (pinfunction "A4_5") (pintype "bidirectional"))
      (node (ref "U5") (pin "30") (pinfunction "GPIO2_25_30") (pintype "passive"))
    )
    (net (code "36") (name "Net-(D1-A)") (class "Default")
      (node (ref "D1") (pin "2") (pinfunction "A_2") (pintype "passive"))
      (node (ref "LED1") (pin "C") (pinfunction "C_C") (pintype "passive"))
      (node (ref "Q1") (pin "3") (pinfunction "C_3") (pintype "passive"))
      (node (ref "RELAY_A") (pin "1") (pinfunction "COIL2_1") (pintype "bidirectional"))
    )
    (net (code "37") (name "Net-(D2-A)") (class "Default")
      (node (ref "D2") (pin "2") (pinfunction "A_2") (pintype "passive"))
      (node (ref "LED2") (pin "C") (pinfunction "C_C") (pintype "passive"))
      (node (ref "Q2") (pin "3") (pinfunction "C_3") (pintype "passive"))
      (node (ref "RELAY_B") (pin "1") (pinfunction "COIL2_1") (pintype "bidirectional"))
    )
    (net (code "38") (name "Net-(D3-A)") (class "Default")
      (node (ref "D3") (pin "2") (pinfunction "A_2") (pintype "passive"))
      (node (ref "LED3") (pin "C") (pinfunction "C_C") (pintype "passive"))
      (node (ref "Q3") (pin "3") (pinfunction "C_3") (pintype "passive"))
      (node (ref "RELAY_C") (pin "1") (pinfunction "COIL2_1") (pintype "bidirectional"))
    )
    (net (code "39") (name "Net-(D4-A)") (class "Default")
      (node (ref "D4") (pin "2") (pinfunction "A_2") (pintype "passive"))
      (node (ref "LED4") (pin "C") (pinfunction "C_C") (pintype "passive"))
      (node (ref "Q4") (pin "3") (pinfunction "C_3") (pintype "passive"))
      (node (ref "RELAY_D") (pin "1") (pinfunction "COIL2_1") (pintype "bidirectional"))
    )
    (net (code "40") (name "Net-(JP3-Pad21)") (class "Default")
      (node (ref "JP3") (pin "21") (pinfunction "21_21") (pintype "passive"))
      (node (ref "U5") (pin "51") (pinfunction "VDD_5V_51") (pintype "power_in"))
    )
    (net (code "41") (name "Net-(JP4-Pad3)") (class "Default")
      (node (ref "JP4") (pin "3") (pinfunction "3_3") (pintype "passive"))
      (node (ref "U5") (pin "52") (pinfunction "VDD_5V_52") (pintype "power_in"))
    )
    (net (code "42") (name "Net-(LED1-PadA)") (class "Default")
      (node (ref "LED1") (pin "A") (pinfunction "A_A") (pintype "passive"))
      (node (ref "R1") (pin "1") (pinfunction "1_1") (pintype "passive"))
    )
    (net (code "43") (name "Net-(LED2-PadA)") (class "Default")
      (node (ref "LED2") (pin "A") (pinfunction "A_A") (pintype "passive"))
      (node (ref "R2") (pin "1") (pinfunction "1_1") (pintype "passive"))
    )
    (net (code "44") (name "Net-(LED3-PadA)") (class "Default")
      (node (ref "LED3") (pin "A") (pinfunction "A_A") (pintype "passive"))
      (node (ref "R3") (pin "1") (pinfunction "1_1") (pintype "passive"))
    )
    (net (code "45") (name "Net-(LED4-PadA)") (class "Default")
      (node (ref "LED4") (pin "A") (pinfunction "A_A") (pintype "passive"))
      (node (ref "R4") (pin "1") (pinfunction "1_1") (pintype "passive"))
    )
    (net (code "46") (name "Net-(LED5-PadA)") (class "Default")
      (node (ref "LED5") (pin "A") (pinfunction "A_A") (pintype "passive"))
      (node (ref "R19") (pin "2") (pinfunction "2_2") (pintype "passive"))
    )
    (net (code "47") (name "Net-(LED6-PadA)") (class "Default")
      (node (ref "LED6") (pin "A") (pinfunction "A_A") (pintype "passive"))
      (node (ref "R13") (pin "1") (pinfunction "1_1") (pintype "passive"))
    )
    (net (code "48") (name "Net-(LED7-PadA)") (class "Default")
      (node (ref "LED7") (pin "A") (pinfunction "A_A") (pintype "passive"))
      (node (ref "R14") (pin "1") (pinfunction "1_1") (pintype "passive"))
    )
    (net (code "49") (name "Net-(LED8-PadA)") (class "Default")
      (node (ref "LED8") (pin "A") (pinfunction "A_A") (pintype "passive"))
      (node (ref "R28") (pin "1") (pinfunction "1_1") (pintype "passive"))
    )
    (net (code "50") (name "Net-(LED9-PadA)") (class "Default")
      (node (ref "LED9") (pin "A") (pinfunction "A_A") (pintype "passive"))
      (node (ref "R31") (pin "1") (pinfunction "1_1") (pintype "passive"))
    )
    (net (code "51") (name "Net-(Q1-B)") (class "Default")
      (node (ref "Q1") (pin "1") (pinfunction "B_1") (pintype "passive"))
      (node (ref "R5") (pin "2") (pinfunction "2_2") (pintype "passive"))
      (node (ref "R6") (pin "2") (pinfunction "2_2") (pintype "passive"))
    )
    (net (code "52") (name "Net-(Q2-B)") (class "Default")
      (node (ref "Q2") (pin "1") (pinfunction "B_1") (pintype "passive"))
      (node (ref "R7") (pin "2") (pinfunction "2_2") (pintype "passive"))
      (node (ref "R8") (pin "2") (pinfunction "2_2") (pintype "passive"))
    )
    (net (code "53") (name "Net-(Q3-B)") (class "Default")
      (node (ref "Q3") (pin "1") (pinfunction "B_1") (pintype "passive"))
      (node (ref "R10") (pin "2") (pinfunction "2_2") (pintype "passive"))
      (node (ref "R9") (pin "2") (pinfunction "2_2") (pintype "passive"))
    )
    (net (code "54") (name "Net-(Q4-B)") (class "Default")
      (node (ref "Q4") (pin "1") (pinfunction "B_1") (pintype "passive"))
      (node (ref "R11") (pin "2") (pinfunction "2_2") (pintype "passive"))
      (node (ref "R12") (pin "2") (pinfunction "2_2") (pintype "passive"))
    )
    (net (code "55") (name "Net-(Q5-B)") (class "Default")
      (node (ref "Q5") (pin "1") (pinfunction "B_1") (pintype "passive"))
      (node (ref "R20") (pin "2") (pinfunction "2_2") (pintype "passive"))
      (node (ref "R21") (pin "2") (pinfunction "2_2") (pintype "passive"))
    )
    (net (code "56") (name "Net-(Q5-C)") (class "Default")
      (node (ref "LED6") (pin "C") (pinfunction "C_C") (pintype "passive"))
      (node (ref "Q5") (pin "3") (pinfunction "C_3") (pintype "passive"))
    )
    (net (code "57") (name "Net-(Q6-B)") (class "Default")
      (node (ref "Q6") (pin "1") (pinfunction "B_1") (pintype "passive"))
      (node (ref "R23") (pin "2") (pinfunction "2_2") (pintype "passive"))
      (node (ref "R24") (pin "2") (pinfunction "2_2") (pintype "passive"))
    )
    (net (code "58") (name "Net-(Q6-C)") (class "Default")
      (node (ref "LED7") (pin "C") (pinfunction "C_C") (pintype "passive"))
      (node (ref "Q6") (pin "3") (pinfunction "C_3") (pintype "passive"))
    )
    (net (code "59") (name "Net-(Q7-B)") (class "Default")
      (node (ref "Q7") (pin "1") (pinfunction "B_1") (pintype "passive"))
      (node (ref "R29") (pin "2") (pinfunction "2_2") (pintype "passive"))
      (node (ref "R30") (pin "2") (pinfunction "2_2") (pintype "passive"))
    )
    (net (code "60") (name "Net-(Q7-C)") (class "Default")
      (node (ref "LED8") (pin "C") (pinfunction "C_C") (pintype "passive"))
      (node (ref "Q7") (pin "3") (pinfunction "C_3") (pintype "passive"))
    )
    (net (code "61") (name "Net-(Q8-B)") (class "Default")
      (node (ref "Q8") (pin "1") (pinfunction "B_1") (pintype "passive"))
      (node (ref "R32") (pin "2") (pinfunction "2_2") (pintype "passive"))
      (node (ref "R33") (pin "2") (pinfunction "2_2") (pintype "passive"))
    )
    (net (code "62") (name "Net-(Q8-C)") (class "Default")
      (node (ref "LED9") (pin "C") (pinfunction "C_C") (pintype "passive"))
      (node (ref "Q8") (pin "3") (pinfunction "C_3") (pintype "passive"))
    )
    (net (code "63") (name "Net-(RELAY_A-MAIN)") (class "Default")
      (node (ref "HEADER-RELAY") (pin "8") (pinfunction "8_8") (pintype "passive"))
      (node (ref "RELAY_A") (pin "2") (pinfunction "MAIN_2") (pintype "bidirectional"))
    )
    (net (code "64") (name "Net-(RELAY_A-NO)") (class "Default")
      (node (ref "HEADER-RELAY") (pin "7") (pinfunction "7_7") (pintype "passive"))
      (node (ref "RELAY_A") (pin "3") (pinfunction "NO_3") (pintype "bidirectional"))
    )
    (net (code "65") (name "Net-(RELAY_B-MAIN)") (class "Default")
      (node (ref "HEADER-RELAY") (pin "6") (pinfunction "6_6") (pintype "passive"))
      (node (ref "RELAY_B") (pin "2") (pinfunction "MAIN_2") (pintype "bidirectional"))
    )
    (net (code "66") (name "Net-(RELAY_B-NO)") (class "Default")
      (node (ref "HEADER-RELAY") (pin "5") (pinfunction "5_5") (pintype "passive"))
      (node (ref "RELAY_B") (pin "3") (pinfunction "NO_3") (pintype "bidirectional"))
    )
    (net (code "67") (name "Net-(RELAY_C-MAIN)") (class "Default")
      (node (ref "HEADER-RELAY") (pin "4") (pinfunction "4_4") (pintype "passive"))
      (node (ref "RELAY_C") (pin "2") (pinfunction "MAIN_2") (pintype "bidirectional"))
    )
    (net (code "68") (name "Net-(RELAY_C-NO)") (class "Default")
      (node (ref "HEADER-RELAY") (pin "3") (pinfunction "3_3") (pintype "passive"))
      (node (ref "RELAY_C") (pin "3") (pinfunction "NO_3") (pintype "bidirectional"))
    )
    (net (code "69") (name "Net-(RELAY_D-MAIN)") (class "Default")
      (node (ref "HEADER-RELAY") (pin "2") (pinfunction "2_2") (pintype "passive"))
      (node (ref "RELAY_D") (pin "2") (pinfunction "MAIN_2") (pintype "bidirectional"))
    )
    (net (code "70") (name "Net-(RELAY_D-NO)") (class "Default")
      (node (ref "HEADER-RELAY") (pin "1") (pinfunction "1_1") (pintype "passive"))
      (node (ref "RELAY_D") (pin "3") (pinfunction "NO_3") (pintype "bidirectional"))
    )
    (net (code "71") (name "Net-(U4-WP)") (class "Default")
      (node (ref "R34") (pin "1") (pinfunction "1_1") (pintype "passive"))
      (node (ref "TP2") (pin "TP") (pinfunction "TP_TP") (pintype "input"))
      (node (ref "U4") (pin "7") (pinfunction "WP_7") (pintype "input"))
    )
    (net (code "72") (name "Net-(U5-AIN0)") (class "Default")
      (node (ref "JP3") (pin "4") (pinfunction "4_4") (pintype "passive"))
      (node (ref "U5") (pin "85") (pinfunction "AIN0_85") (pintype "power_in"))
    )
    (net (code "73") (name "Net-(U5-AIN1)") (class "Default")
      (node (ref "JP4") (pin "20") (pinfunction "20_20") (pintype "passive"))
      (node (ref "U5") (pin "86") (pinfunction "AIN1_86") (pintype "input"))
    )
    (net (code "74") (name "Net-(U5-AIN2)") (class "Default")
      (node (ref "JP3") (pin "5") (pinfunction "5_5") (pintype "passive"))
      (node (ref "U5") (pin "83") (pinfunction "AIN2_83") (pintype "passive"))
    )
    (net (code "75") (name "Net-(U5-AIN3)") (class "Default")
      (node (ref "JP4") (pin "19") (pinfunction "19_19") (pintype "passive"))
      (node (ref "U5") (pin "84") (pinfunction "AIN3_84") (pintype "power_in"))
    )
    (net (code "76") (name "Net-(U5-AIN4)") (class "Default")
      (node (ref "JP3") (pin "7") (pinfunction "7_7") (pintype "passive"))
      (node (ref "U5") (pin "79") (pinfunction "AIN4_79") (pintype "passive"))
    )
    (net (code "77") (name "Net-(U5-AIN5)") (class "Default")
      (node (ref "JP4") (pin "18") (pinfunction "18_18") (pintype "passive"))
      (node (ref "U5") (pin "82") (pinfunction "AIN5_82") (pintype "passive"))
    )
    (net (code "78") (name "Net-(U5-AIN6)") (class "Default")
      (node (ref "JP3") (pin "6") (pinfunction "6_6") (pintype "passive"))
      (node (ref "U5") (pin "81") (pinfunction "AIN6_81") (pintype "passive"))
    )
    (net (code "79") (name "Net-(U5-CLKOUT2)") (class "Default")
      (node (ref "JP3") (pin "3") (pinfunction "3_3") (pintype "passive"))
      (node (ref "U5") (pin "87") (pinfunction "CLKOUT2_87") (pintype "input"))
    )
    (net (code "80") (name "Net-(U5-EHRPWM1A)") (class "Default")
      (node (ref "JP4") (pin "7") (pinfunction "7_7") (pintype "passive"))
      (node (ref "U5") (pin "60") (pinfunction "EHRPWM1A_60") (pintype "passive"))
    )
    (net (code "81") (name "Net-(U5-EHRPWM1B)") (class "Default")
      (node (ref "JP4") (pin "8") (pinfunction "8_8") (pintype "passive"))
      (node (ref "U5") (pin "62") (pinfunction "EHRPWM1B_62") (pintype "passive"))
    )
    (net (code "82") (name "Net-(U5-EHRPWM2A)") (class "Default")
      (node (ref "JP1") (pin "14") (pinfunction "14_14") (pintype "passive"))
      (node (ref "U5") (pin "19") (pinfunction "EHRPWM2A_19") (pintype "passive"))
    )
    (net (code "83") (name "Net-(U5-EHRPWM2B)") (class "Default")
      (node (ref "JP1") (pin "17") (pinfunction "17_17") (pintype "passive"))
      (node (ref "U5") (pin "13") (pinfunction "EHRPWM2B_13") (pintype "passive"))
    )
    (net (code "84") (name "Net-(U5-GNDA_ADC)") (class "Default")
      (node (ref "JP4") (pin "17") (pinfunction "17_17") (pintype "passive"))
      (node (ref "U5") (pin "80") (pinfunction "GNDA_ADC_80") (pintype "passive"))
    )
    (net (code "85") (name "Net-(U5-GPIO0_7)") (class "Default")
      (node (ref "JP4") (pin "21") (pinfunction "21_21") (pintype "passive"))
      (node (ref "U5") (pin "88") (pinfunction "GPIO0_7_88") (pintype "input"))
    )
    (net (code "86") (name "Net-(U5-GPIO1_13)") (class "Default")
      (node (ref "JP1") (pin "18") (pinfunction "18_18") (pintype "passive"))
      (node (ref "U5") (pin "11") (pinfunction "GPIO1_13_11") (pintype "passive"))
    )
    (net (code "87") (name "Net-(U5-GPIO1_15)") (class "Default")
      (node (ref "JP1") (pin "16") (pinfunction "16_16") (pintype "passive"))
      (node (ref "U5") (pin "15") (pinfunction "GPIO1_15_15") (pintype "passive"))
    )
    (net (code "88") (name "Net-(U5-GPIO1_16)") (class "Default")
      (node (ref "JP3") (pin "16") (pinfunction "16_16") (pintype "passive"))
      (node (ref "U5") (pin "61") (pinfunction "GPIO1_16_61") (pintype "passive"))
    )
    (net (code "89") (name "Net-(U5-GPIO1_28)") (class "Default")
      (node (ref "JP4") (pin "6") (pinfunction "6_6") (pintype "passive"))
      (node (ref "U5") (pin "58") (pinfunction "GPIO1_28_58") (pintype "passive"))
    )
    (net (code "90") (name "Net-(U5-GPIO2_6)") (class "Default")
      (node (ref "JP1") (pin "1") (pinfunction "1_1") (pintype "passive"))
      (node (ref "U5") (pin "45") (pinfunction "GPIO2_6_45") (pintype "power_in"))
    )
    (net (code "91") (name "Net-(U5-GPIO2_7)") (class "Default")
      (node (ref "JP2") (pin "23") (pinfunction "23_23") (pintype "passive"))
      (node (ref "U5") (pin "46") (pinfunction "GPIO2_7_46") (pintype "power_in"))
    )
    (net (code "92") (name "Net-(U5-GPIO2_8)") (class "Default")
      (node (ref "JP1") (pin "2") (pinfunction "2_2") (pintype "passive"))
      (node (ref "U5") (pin "43") (pinfunction "GPIO2_8_43") (pintype "power_in"))
    )
    (net (code "93") (name "Net-(U5-GPIO2_9)") (class "Default")
      (node (ref "JP2") (pin "22") (pinfunction "22_22") (pintype "passive"))
      (node (ref "U5") (pin "44") (pinfunction "GPIO2_9_44") (pintype "power_in"))
    )
    (net (code "94") (name "Net-(U5-GPIO2_10)") (class "Default")
      (node (ref "JP1") (pin "3") (pinfunction "3_3") (pintype "passive"))
      (node (ref "U5") (pin "41") (pinfunction "GPIO2_10_41") (pintype "passive"))
    )
    (net (code "95") (name "Net-(U5-GPIO2_11)") (class "Default")
      (node (ref "JP2") (pin "21") (pinfunction "21_21") (pintype "passive"))
      (node (ref "U5") (pin "42") (pinfunction "GPIO2_11_42") (pintype "power_in"))
    )
    (net (code "96") (name "Net-(U5-GPIO2_12)") (class "Default")
      (node (ref "JP1") (pin "4") (pinfunction "4_4") (pintype "passive"))
      (node (ref "U5") (pin "39") (pinfunction "GPIO2_12_39") (pintype "passive"))
    )
    (net (code "97") (name "Net-(U5-GPIO2_13)") (class "Default")
      (node (ref "JP2") (pin "20") (pinfunction "20_20") (pintype "passive"))
      (node (ref "U5") (pin "40") (pinfunction "GPIO2_13_40") (pintype "passive"))
    )
    (net (code "98") (name "Net-(U5-GPIO3_19)") (class "Default")
      (node (ref "JP3") (pin "10") (pinfunction "10_10") (pintype "passive"))
      (node (ref "U5") (pin "73") (pinfunction "GPIO3_19_73") (pintype "passive"))
    )
    (net (code "99") (name "Net-(U5-PWR_BUT)") (class "Default")
      (node (ref "JP3") (pin "19") (pinfunction "19_19") (pintype "passive"))
      (node (ref "U5") (pin "55") (pinfunction "PWR_BUT_55") (pintype "passive"))
    )
    (net (code "100") (name "Net-(U5-SPI1_CS0)") (class "Default")
      (node (ref "JP4") (pin "14") (pinfunction "14_14") (pintype "passive"))
      (node (ref "U5") (pin "74") (pinfunction "SPI1_CS0_74") (pintype "passive"))
    )
    (net (code "101") (name "Net-(U5-SPI1_DI)") (class "Default")
      (node (ref "JP4") (pin "15") (pinfunction "15_15") (pintype "passive"))
      (node (ref "U5") (pin "76") (pinfunction "SPI1_DI_76") (pintype "passive"))
    )
    (net (code "102") (name "Net-(U5-SPI1_DO)") (class "Default")
      (node (ref "JP3") (pin "9") (pinfunction "9_9") (pintype "passive"))
      (node (ref "U5") (pin "75") (pinfunction "SPI1_DO_75") (pintype "passive"))
    )
    (net (code "103") (name "Net-(U5-SPI1_SCLK)") (class "Default")
      (node (ref "JP3") (pin "8") (pinfunction "8_8") (pintype "passive"))
      (node (ref "U5") (pin "77") (pinfunction "SPI1_SCLK_77") (pintype "passive"))
    )
    (net (code "104") (name "Net-(U5-SYS_RESETN)") (class "Default")
      (node (ref "JP4") (pin "5") (pinfunction "5_5") (pintype "passive"))
      (node (ref "U5") (pin "56") (pinfunction "SYS_RESETN_56") (pintype "passive"))
    )
    (net (code "105") (name "Net-(U5-TIMER4)") (class "Default")
      (node (ref "JP1") (pin "20") (pinfunction "20_20") (pintype "passive"))
      (node (ref "U5") (pin "7") (pinfunction "TIMER4_7") (pintype "passive"))
    )
    (net (code "106") (name "Net-(U5-TIMER5)") (class "Default")
      (node (ref "JP1") (pin "19") (pinfunction "19_19") (pintype "passive"))
      (node (ref "U5") (pin "9") (pinfunction "TIMER5_9") (pintype "passive"))
    )
    (net (code "107") (name "Net-(U5-TIMER6)") (class "Default")
      (node (ref "JP2") (pin "5") (pinfunction "5_5") (pintype "passive"))
      (node (ref "U5") (pin "10") (pinfunction "TIMER6_10") (pintype "passive"))
    )
    (net (code "108") (name "Net-(U5-TIMER7)") (class "Default")
      (node (ref "JP2") (pin "4") (pinfunction "4_4") (pintype "passive"))
      (node (ref "U5") (pin "8") (pinfunction "TIMER7_8") (pintype "passive"))
    )
    (net (code "109") (name "Net-(U5-UART1_RXD)") (class "Default")
      (node (ref "JP4") (pin "13") (pinfunction "13_13") (pintype "passive"))
      (node (ref "U5") (pin "72") (pinfunction "UART1_RXD_72") (pintype "passive"))
    )
    (net (code "110") (name "Net-(U5-UART1_TXD)") (class "Default")
      (node (ref "JP4") (pin "12") (pinfunction "12_12") (pintype "passive"))
      (node (ref "U5") (pin "70") (pinfunction "UART1_TXD_70") (pintype "passive"))
    )
    (net (code "111") (name "Net-(U5-UART2_RXD)") (class "Default")
      (node (ref "JP4") (pin "11") (pinfunction "11_11") (pintype "passive"))
      (node (ref "U5") (pin "68") (pinfunction "UART2_RXD_68") (pintype "passive"))
    )
    (net (code "112") (name "Net-(U5-UART2_TXD)") (class "Default")
      (node (ref "JP3") (pin "13") (pinfunction "13_13") (pintype "passive"))
      (node (ref "U5") (pin "67") (pinfunction "UART2_TXD_67") (pintype "passive"))
    )
    (net (code "113") (name "Net-(U5-UART3_CTSN)") (class "Default")
      (node (ref "JP2") (pin "18") (pinfunction "18_18") (pintype "passive"))
      (node (ref "U5") (pin "36") (pinfunction "UART3_CTSN_36") (pintype "passive"))
    )
    (net (code "114") (name "Net-(U5-UART3_RTSN)") (class "Default")
      (node (ref "JP2") (pin "17") (pinfunction "17_17") (pintype "passive"))
      (node (ref "U5") (pin "34") (pinfunction "UART3_RTSN_34") (pintype "passive"))
    )
    (net (code "115") (name "Net-(U5-UART4_CTSN)") (class "Default")
      (node (ref "JP1") (pin "6") (pinfunction "6_6") (pintype "passive"))
      (node (ref "U5") (pin "35") (pinfunction "UART4_CTSN_35") (pintype "passive"))
    )
    (net (code "116") (name "Net-(U5-UART4_RTSN)") (class "Default")
      (node (ref "JP1") (pin "7") (pinfunction "7_7") (pintype "passive"))
      (node (ref "U5") (pin "33") (pinfunction "UART4_RTSN_33") (pintype "passive"))
    )
    (net (code "117") (name "Net-(U5-UART4_RXD)") (class "Default")
      (node (ref "JP3") (pin "18") (pinfunction "18_18") (pintype "passive"))
      (node (ref "U5") (pin "57") (pinfunction "UART4_RXD_57") (pintype "passive"))
    )
    (net (code "118") (name "Net-(U5-UART4_TXD)") (class "Default")
      (node (ref "JP3") (pin "17") (pinfunction "17_17") (pintype "passive"))
      (node (ref "U5") (pin "59") (pinfunction "UART4_TXD_59") (pintype "passive"))
    )
    (net (code "119") (name "Net-(U5-UART5_CTSN)") (class "Default")
      (node (ref "JP1") (pin "8") (pinfunction "8_8") (pintype "passive"))
      (node (ref "U5") (pin "31") (pinfunction "UART5_CTSN_31") (pintype "passive"))
    )
    (net (code "120") (name "Net-(U5-UART5_RTSN)") (class "Default")
      (node (ref "JP2") (pin "16") (pinfunction "16_16") (pintype "passive"))
      (node (ref "U5") (pin "32") (pinfunction "UART5_RTSN_32") (pintype "passive"))
    )
    (net (code "121") (name "Net-(U5-UART5_RXD)") (class "Default")
      (node (ref "JP2") (pin "19") (pinfunction "19_19") (pintype "passive"))
      (node (ref "U5") (pin "38") (pinfunction "UART5_RXD_38") (pintype "passive"))
    )
    (net (code "122") (name "Net-(U5-UART5_TXD)") (class "Default")
      (node (ref "JP1") (pin "5") (pinfunction "5_5") (pintype "passive"))
      (node (ref "U5") (pin "37") (pinfunction "UART5_TXD_37") (pintype "passive"))
    )
    (net (code "123") (name "Net-(U5-VDD_ADC)") (class "Default")
      (node (ref "JP4") (pin "16") (pinfunction "16_16") (pintype "passive"))
      (node (ref "U5") (pin "78") (pinfunction "VDD_ADC_78") (pintype "passive"))
    )
    (net (code "124") (name "ONEWIRE_A") (class "Default")
      (node (ref "Q9") (pin "3") (pinfunction "D1_3") (pintype "passive"))
      (node (ref "R18") (pin "1") (pinfunction "1_1") (pintype "passive"))
      (node (ref "R26") (pin "1") (pinfunction "1_1") (pintype "passive"))
      (node (ref "RJ1") (pin "1") (pinfunction "1_1") (pintype "bidirectional"))
      (node (ref "RJ2") (pin "1") (pinfunction "1_1") (pintype "bidirectional"))
      (node (ref "U1") (pin "1") (pinfunction "DQ_1") (pintype "bidirectional"))
    )
    (net (code "125") (name "ONEWIRE_A_3P3") (class "Default")
      (node (ref "JP1") (pin "22") (pinfunction "22_22") (pintype "passive"))
      (node (ref "Q9") (pin "2") (pinfunction "S_2") (pintype "passive"))
      (node (ref "R17") (pin "1") (pinfunction "1_1") (pintype "passive"))
      (node (ref "U5") (pin "3") (pinfunction "GPIO1_6_3") (pintype "power_in"))
    )
    (net (code "126") (name "ONEWIRE_B") (class "Default")
      (node (ref "Q10") (pin "3") (pinfunction "D1_3") (pintype "passive"))
      (node (ref "R27") (pin "1") (pinfunction "1_1") (pintype "passive"))
      (node (ref "R40") (pin "1") (pinfunction "1_1") (pintype "passive"))
      (node (ref "RJ1") (pin "4") (pinfunction "4_4") (pintype "bidirectional"))
      (node (ref "RJ2") (pin "4") (pinfunction "4_4") (pintype "bidirectional"))
    )
    (net (code "127") (name "ONEWIRE_B_3P3") (class "Default")
      (node (ref "JP1") (pin "21") (pinfunction "21_21") (pintype "passive"))
      (node (ref "Q10") (pin "2") (pinfunction "S_2") (pintype "passive"))
      (node (ref "R39") (pin "1") (pinfunction "1_1") (pintype "passive"))
      (node (ref "U5") (pin "5") (pinfunction "GPIO1_2_5") (pintype "passive"))
    )
    (net (code "128") (name "RELAY_A") (class "Default")
      (node (ref "R5") (pin "1") (pinfunction "1_1") (pintype "passive"))
      (node (ref "U3") (pin "17") (pinfunction "B3_17") (pintype "bidirectional"))
    )
    (net (code "129") (name "RELAY_A_3P3") (class "Default")
      (node (ref "JP2") (pin "10") (pinfunction "10_10") (pintype "passive"))
      (node (ref "U3") (pin "4") (pinfunction "A3_4") (pintype "bidirectional"))
      (node (ref "U5") (pin "20") (pinfunction "GPIO1_31_20") (pintype "passive"))
    )
    (net (code "130") (name "RELAY_B") (class "Default")
      (node (ref "R7") (pin "1") (pinfunction "1_1") (pintype "passive"))
      (node (ref "U3") (pin "16") (pinfunction "B4_16") (pintype "bidirectional"))
    )
    (net (code "131") (name "RELAY_B_3P3") (class "Default")
      (node (ref "JP2") (pin "11") (pinfunction "11_11") (pintype "passive"))
      (node (ref "U3") (pin "5") (pinfunction "A4_5") (pintype "bidirectional"))
      (node (ref "U5") (pin "22") (pinfunction "GPIO1_5_22") (pintype "passive"))
    )
    (net (code "132") (name "RELAY_C") (class "Default")
      (node (ref "R9") (pin "1") (pinfunction "1_1") (pintype "passive"))
      (node (ref "U3") (pin "15") (pinfunction "B5_15") (pintype "bidirectional"))
    )
    (net (code "133") (name "RELAY_C_3P3") (class "Default")
      (node (ref "JP2") (pin "12") (pinfunction "12_12") (pintype "passive"))
      (node (ref "U3") (pin "6") (pinfunction "A5_6") (pintype "bidirectional"))
      (node (ref "U5") (pin "24") (pinfunction "GPIO1_1_24") (pintype "passive"))
    )
    (net (code "134") (name "RELAY_D") (class "Default")
      (node (ref "R11") (pin "1") (pinfunction "1_1") (pintype "passive"))
      (node (ref "U3") (pin "14") (pinfunction "B6_14") (pintype "bidirectional"))
    )
    (net (code "135") (name "RELAY_D_3P3") (class "Default")
      (node (ref "JP2") (pin "13") (pinfunction "13_13") (pintype "passive"))
      (node (ref "U3") (pin "7") (pinfunction "A6_7") (pintype "bidirectional"))
      (node (ref "U5") (pin "26") (pinfunction "GPIO1_29_26") (pintype "passive"))
    )
    (net (code "136") (name "RESET") (class "Default")
      (node (ref "GPO") (pin "2") (pinfunction "2_2") (pintype "passive"))
      (node (ref "SW1") (pin "3") (pinfunction "3_3") (pintype "passive"))
      (node (ref "SW1") (pin "4") (pinfunction "4_4") (pintype "passive"))
      (node (ref "U3") (pin "12") (pinfunction "B8_12") (pintype "bidirectional"))
    )
    (net (code "137") (name "RESET_3P3") (class "Default")
      (node (ref "JP3") (pin "11") (pinfunction "11_11") (pintype "passive"))
      (node (ref "U3") (pin "9") (pinfunction "A8_9") (pintype "bidirectional"))
      (node (ref "U5") (pin "71") (pinfunction "GPIO3_21_71") (pintype "passive"))
    )
    (net (code "138") (name "TEST_PULSE") (class "Default")
      (node (ref "TEST_A") (pin "1") (pinfunction "1_1") (pintype "passive"))
      (node (ref "TEST_B") (pin "1") (pinfunction "1_1") (pintype "passive"))
      (node (ref "TEST_C") (pin "1") (pinfunction "1_1") (pintype "passive"))
      (node (ref "TEST_D") (pin "1") (pinfunction "1_1") (pintype "passive"))
      (node (ref "U3") (pin "18") (pinfunction "B2_18") (pintype "bidirectional"))
    )
    (net (code "139") (name "TEST_PULSE_3P3") (class "Default")
      (node (ref "JP1") (pin "9") (pinfunction "9_9") (pintype "passive"))
      (node (ref "U3") (pin "3") (pinfunction "A2_3") (pintype "bidirectional"))
      (node (ref "U5") (pin "29") (pinfunction "GPIO2_23_29") (pintype "passive"))
    )
    (net (code "140") (name "unconnected-(RELAY_A-NC-Pad4)") (class "Default")
      (node (ref "RELAY_A") (pin "4") (pinfunction "NC_4") (pintype "bidirectional"))
    )
    (net (code "141") (name "unconnected-(RELAY_B-NC-Pad4)") (class "Default")
      (node (ref "RELAY_B") (pin "4") (pinfunction "NC_4") (pintype "bidirectional"))
    )
    (net (code "142") (name "unconnected-(RELAY_C-NC-Pad4)") (class "Default")
      (node (ref "RELAY_C") (pin "4") (pinfunction "NC_4") (pintype "bidirectional"))
    )
    (net (code "143") (name "unconnected-(RELAY_D-NC-Pad4)") (class "Default")
      (node (ref "RELAY_D") (pin "4") (pinfunction "NC_4") (pintype "bidirectional"))
    )
  )
)
